# PCB-MicroTally.net
KiCad netlist of a schematic drawn in EAGLE
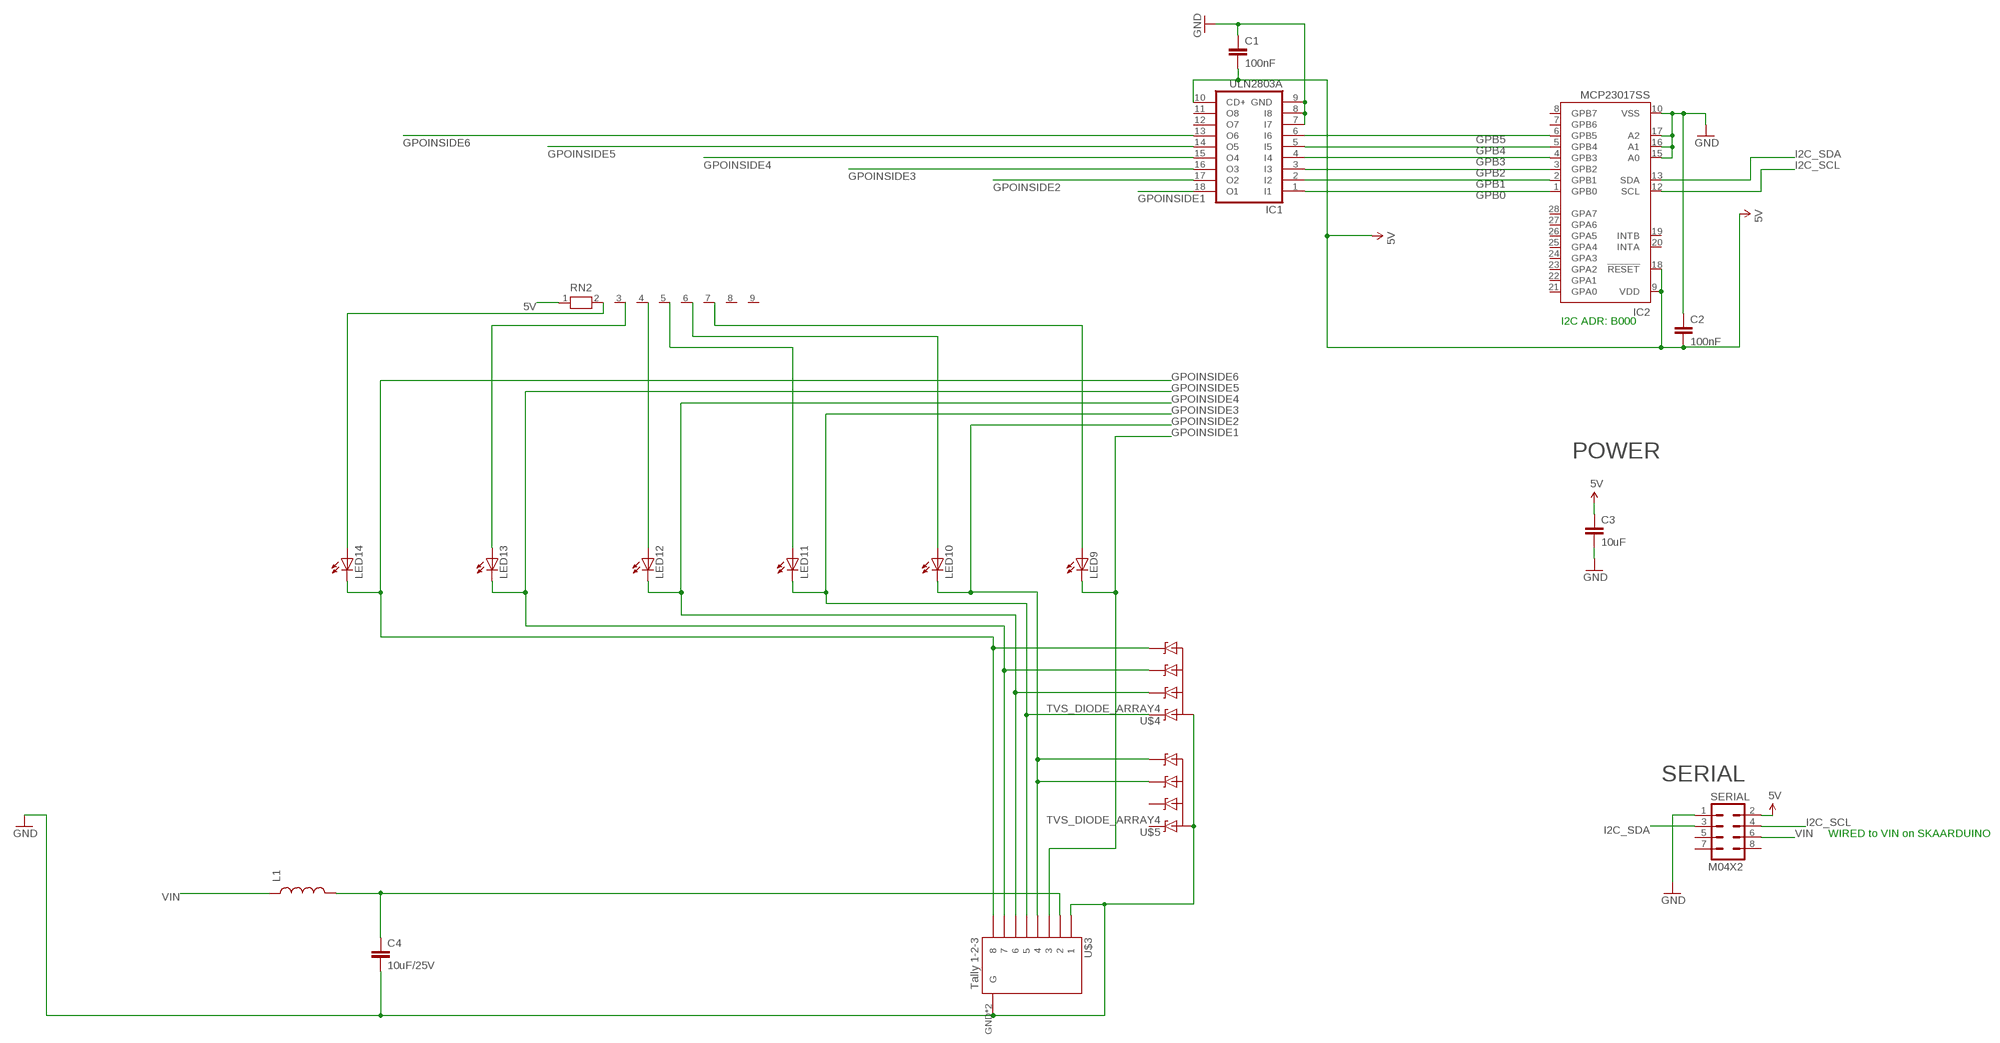
[diagram p0: schematic, sheet 1]

(export (version "E")
  (design (tool "Eeschema 10.0.6"))
  (components
    (comp (ref "C1")
      (value "100nF")
      (footprint "eagle-import:0805")
      (libsource (lib "eagle-import") (part "CAP0805"))
    )
    (comp (ref "C2")
      (value "100nF")
      (footprint "eagle-import:0603-CAP")
      (libsource (lib "eagle-import") (part "CAP0603-CAP"))
    )
    (comp (ref "C3")
      (value "10uF")
      (footprint "eagle-import:0805")
      (libsource (lib "eagle-import") (part "CAP0805"))
    )
    (comp (ref "C4")
      (value "10uF/25V")
      (footprint "eagle-import:0805")
      (libsource (lib "eagle-import") (part "CAP0805"))
    )
    (comp (ref "IC1")
      (value "ULN2803A")
      (footprint "eagle-import:SO18W")
      (libsource (lib "eagle-import") (part "ULN2803ASO18W"))
    )
    (comp (ref "IC2")
      (value "MCP23017SS")
      (footprint "eagle-import:SSOP28")
      (fields (field (name "MF") "MICROCHIP") (field (name "MPN") "MCP23017-E/SS"))
      (libsource (lib "eagle-import") (part "MCP23017SS"))
    )
    (comp (ref "L1")
      (value "INDUCTOR0805")
      (footprint "eagle-import:0805")
      (libsource (lib "eagle-import") (part "INDUCTOR0805"))
    )
    (comp (ref "LED9")
      (value "LED3MM")
      (footprint "eagle-import:LED3MM")
      (libsource (lib "eagle-import") (part "LED3MM"))
    )
    (comp (ref "LED10")
      (value "LED3MM")
      (footprint "eagle-import:LED3MM")
      (libsource (lib "eagle-import") (part "LED3MM"))
    )
    (comp (ref "LED11")
      (value "LED3MM")
      (footprint "eagle-import:LED3MM")
      (libsource (lib "eagle-import") (part "LED3MM"))
    )
    (comp (ref "LED12")
      (value "LED3MM")
      (footprint "eagle-import:LED3MM")
      (libsource (lib "eagle-import") (part "LED3MM"))
    )
    (comp (ref "LED13")
      (value "LED3MM")
      (footprint "eagle-import:LED3MM")
      (libsource (lib "eagle-import") (part "LED3MM"))
    )
    (comp (ref "LED14")
      (value "LED3MM")
      (footprint "eagle-import:LED3MM")
      (libsource (lib "eagle-import") (part "LED3MM"))
    )
    (comp (ref "RN2")
      (value "RN08")
      (footprint "eagle-import:RN-9")
      (libsource (lib "eagle-import") (part "RN08"))
    )
    (comp (ref "SERIAL")
      (value "M04X2")
      (footprint "eagle-import:2X4")
      (libsource (lib "eagle-import") (part "M04X2"))
    )
    (comp (ref "U$3")
      (value "Tally 1-2-3")
      (footprint "eagle-import:RJ45-8_GND_UPRIGHT")
      (libsource (lib "eagle-import") (part "RJ45-8_GNDUPRIGHT"))
    )
    (comp (ref "U$4")
      (value "TVS_DIODE_ARRAY4")
      (footprint "eagle-import:SOT23-6L")
      (libsource (lib "eagle-import") (part "TVS_DIODE_ARRAY4"))
    )
    (comp (ref "U$5")
      (value "TVS_DIODE_ARRAY4")
      (footprint "eagle-import:SOT23-6L")
      (libsource (lib "eagle-import") (part "TVS_DIODE_ARRAY4"))
    )
  )
  (nets
    (net (code "1") (name "/GPB0") (class "Default")
      (node (ref "IC1") (pin "1") (pinfunction "I1_1") (pintype "input"))
      (node (ref "IC2") (pin "1") (pinfunction "GPB0_1") (pintype "bidirectional"))
    )
    (net (code "2") (name "/GPB1") (class "Default")
      (node (ref "IC1") (pin "2") (pinfunction "I2_2") (pintype "input"))
      (node (ref "IC2") (pin "2") (pinfunction "GPB1_2") (pintype "bidirectional"))
    )
    (net (code "3") (name "/GPB2") (class "Default")
      (node (ref "IC1") (pin "3") (pinfunction "I3_3") (pintype "input"))
      (node (ref "IC2") (pin "3") (pinfunction "GPB2_3") (pintype "bidirectional"))
    )
    (net (code "4") (name "/GPB3") (class "Default")
      (node (ref "IC1") (pin "4") (pinfunction "I4_4") (pintype "input"))
      (node (ref "IC2") (pin "4") (pinfunction "GPB3_4") (pintype "bidirectional"))
    )
    (net (code "5") (name "/GPB4") (class "Default")
      (node (ref "IC1") (pin "5") (pinfunction "I5_5") (pintype "input"))
      (node (ref "IC2") (pin "5") (pinfunction "GPB4_5") (pintype "bidirectional"))
    )
    (net (code "6") (name "/GPB5") (class "Default")
      (node (ref "IC1") (pin "6") (pinfunction "I6_6") (pintype "input"))
      (node (ref "IC2") (pin "6") (pinfunction "GPB5_6") (pintype "bidirectional"))
    )
    (net (code "7") (name "/GPOINSIDE1") (class "Default")
      (node (ref "IC1") (pin "18") (pinfunction "O1_18") (pintype "open_collector"))
      (node (ref "LED9") (pin "K") (pinfunction "C_K") (pintype "passive"))
      (node (ref "U$3") (pin "3") (pinfunction "3_3") (pintype "bidirectional"))
    )
    (net (code "8") (name "/GPOINSIDE2") (class "Default")
      (node (ref "IC1") (pin "17") (pinfunction "O2_17") (pintype "open_collector"))
      (node (ref "LED10") (pin "K") (pinfunction "C_K") (pintype "passive"))
      (node (ref "U$3") (pin "4") (pinfunction "4_4") (pintype "bidirectional"))
      (node (ref "U$5") (pin "4") (pinfunction "C_4") (pintype "passive"))
      (node (ref "U$5") (pin "6") (pinfunction "D_6") (pintype "passive"))
    )
    (net (code "9") (name "/GPOINSIDE3") (class "Default")
      (node (ref "IC1") (pin "16") (pinfunction "O3_16") (pintype "open_collector"))
      (node (ref "LED11") (pin "K") (pinfunction "C_K") (pintype "passive"))
      (node (ref "U$3") (pin "5") (pinfunction "5_5") (pintype "bidirectional"))
      (node (ref "U$4") (pin "1") (pinfunction "A_1") (pintype "passive"))
    )
    (net (code "10") (name "/GPOINSIDE4") (class "Default")
      (node (ref "IC1") (pin "15") (pinfunction "O4_15") (pintype "open_collector"))
      (node (ref "LED12") (pin "K") (pinfunction "C_K") (pintype "passive"))
      (node (ref "U$3") (pin "6") (pinfunction "6_6") (pintype "bidirectional"))
      (node (ref "U$4") (pin "3") (pinfunction "B_3") (pintype "passive"))
    )
    (net (code "11") (name "/GPOINSIDE5") (class "Default")
      (node (ref "IC1") (pin "14") (pinfunction "O5_14") (pintype "open_collector"))
      (node (ref "LED13") (pin "K") (pinfunction "C_K") (pintype "passive"))
      (node (ref "U$3") (pin "7") (pinfunction "7_7") (pintype "bidirectional"))
      (node (ref "U$4") (pin "4") (pinfunction "C_4") (pintype "passive"))
    )
    (net (code "12") (name "/GPOINSIDE6") (class "Default")
      (node (ref "IC1") (pin "13") (pinfunction "O6_13") (pintype "open_collector"))
      (node (ref "LED14") (pin "K") (pinfunction "C_K") (pintype "passive"))
      (node (ref "U$3") (pin "8") (pinfunction "8_8") (pintype "bidirectional"))
      (node (ref "U$4") (pin "6") (pinfunction "D_6") (pintype "passive"))
    )
    (net (code "13") (name "/I2C_SCL") (class "Default")
      (node (ref "IC2") (pin "12") (pinfunction "SCL_12") (pintype "input"))
      (node (ref "SERIAL") (pin "4") (pinfunction "4_4") (pintype "passive"))
    )
    (net (code "14") (name "/I2C_SDA") (class "Default")
      (node (ref "IC2") (pin "13") (pinfunction "SDA_13") (pintype "bidirectional"))
      (node (ref "SERIAL") (pin "3") (pinfunction "3_3") (pintype "passive"))
    )
    (net (code "15") (name "/VIN") (class "Default")
      (node (ref "L1") (pin "1") (pinfunction "1_1") (pintype "passive"))
      (node (ref "SERIAL") (pin "6") (pinfunction "6_6") (pintype "passive"))
    )
    (net (code "16") (name "5V") (class "Default")
      (node (ref "C1") (pin "2") (pinfunction "2_2") (pintype "passive"))
      (node (ref "C2") (pin "2") (pinfunction "2_2") (pintype "passive"))
      (node (ref "C3") (pin "1") (pinfunction "1_1") (pintype "passive"))
      (node (ref "IC1") (pin "10") (pinfunction "CD+_10") (pintype "passive"))
      (node (ref "IC2") (pin "18") (pinfunction "~{RESET}_18") (pintype "input"))
      (node (ref "IC2") (pin "9") (pinfunction "VDD_9") (pintype "power_in"))
      (node (ref "RN2") (pin "1") (pinfunction "1_1") (pintype "passive"))
      (node (ref "SERIAL") (pin "2") (pinfunction "2_2") (pintype "passive"))
    )
    (net (code "17") (name "GND") (class "Default")
      (node (ref "C1") (pin "1") (pinfunction "1_1") (pintype "passive"))
      (node (ref "C2") (pin "1") (pinfunction "1_1") (pintype "passive"))
      (node (ref "C3") (pin "2") (pinfunction "2_2") (pintype "passive"))
      (node (ref "C4") (pin "2") (pinfunction "2_2") (pintype "passive"))
      (node (ref "IC1") (pin "7") (pinfunction "I7_7") (pintype "input"))
      (node (ref "IC1") (pin "8") (pinfunction "I8_8") (pintype "input"))
      (node (ref "IC1") (pin "9") (pinfunction "GND_9") (pintype "power_in"))
      (node (ref "IC2") (pin "10") (pinfunction "VSS_10") (pintype "power_in"))
      (node (ref "IC2") (pin "15") (pinfunction "A0_15") (pintype "input"))
      (node (ref "IC2") (pin "16") (pinfunction "A1_16") (pintype "input"))
      (node (ref "IC2") (pin "17") (pinfunction "A2_17") (pintype "input"))
      (node (ref "SERIAL") (pin "1") (pinfunction "1_1") (pintype "passive"))
      (node (ref "U$3") (pin "1") (pinfunction "1_1") (pintype "bidirectional"))
      (node (ref "U$3") (pin "GND") (pinfunction "G_GND") (pintype "power_in"))
      (node (ref "U$3") (pin "GND1") (pinfunction "G_GND1") (pintype "power_in"))
      (node (ref "U$4") (pin "2") (pinfunction "GND_2") (pintype "passive"))
      (node (ref "U$4") (pin "5") (pinfunction "GND_5") (pintype "passive"))
      (node (ref "U$5") (pin "2") (pinfunction "GND_2") (pintype "passive"))
      (node (ref "U$5") (pin "5") (pinfunction "GND_5") (pintype "passive"))
    )
    (net (code "18") (name "Net-(C4-Pad1)") (class "Default")
      (node (ref "C4") (pin "1") (pinfunction "1_1") (pintype "passive"))
      (node (ref "L1") (pin "2") (pinfunction "2_2") (pintype "passive"))
      (node (ref "U$3") (pin "2") (pinfunction "2_2") (pintype "bidirectional"))
    )
    (net (code "19") (name "Net-(LED9-PadA)") (class "Default")
      (node (ref "LED9") (pin "A") (pinfunction "A_A") (pintype "passive"))
      (node (ref "RN2") (pin "7") (pinfunction "7_7") (pintype "passive"))
    )
    (net (code "20") (name "Net-(LED10-PadA)") (class "Default")
      (node (ref "LED10") (pin "A") (pinfunction "A_A") (pintype "passive"))
      (node (ref "RN2") (pin "6") (pinfunction "6_6") (pintype "passive"))
    )
    (net (code "21") (name "Net-(LED11-PadA)") (class "Default")
      (node (ref "LED11") (pin "A") (pinfunction "A_A") (pintype "passive"))
      (node (ref "RN2") (pin "5") (pinfunction "5_5") (pintype "passive"))
    )
    (net (code "22") (name "Net-(LED12-PadA)") (class "Default")
      (node (ref "LED12") (pin "A") (pinfunction "A_A") (pintype "passive"))
      (node (ref "RN2") (pin "4") (pinfunction "4_4") (pintype "passive"))
    )
    (net (code "23") (name "Net-(LED13-PadA)") (class "Default")
      (node (ref "LED13") (pin "A") (pinfunction "A_A") (pintype "passive"))
      (node (ref "RN2") (pin "3") (pinfunction "3_3") (pintype "passive"))
    )
    (net (code "24") (name "Net-(LED14-PadA)") (class "Default")
      (node (ref "LED14") (pin "A") (pinfunction "A_A") (pintype "passive"))
      (node (ref "RN2") (pin "2") (pinfunction "2_2") (pintype "passive"))
    )
    (net (code "25") (name "unconnected-(IC1-O7-Pad12)") (class "Default")
      (node (ref "IC1") (pin "12") (pinfunction "O7_12") (pintype "open_collector"))
    )
    (net (code "26") (name "unconnected-(IC1-O8-Pad11)") (class "Default")
      (node (ref "IC1") (pin "11") (pinfunction "O8_11") (pintype "open_collector"))
    )
    (net (code "27") (name "unconnected-(IC2-GPA0-Pad21)") (class "Default")
      (node (ref "IC2") (pin "21") (pinfunction "GPA0_21") (pintype "bidirectional"))
    )
    (net (code "28") (name "unconnected-(IC2-GPA1-Pad22)") (class "Default")
      (node (ref "IC2") (pin "22") (pinfunction "GPA1_22") (pintype "bidirectional"))
    )
    (net (code "29") (name "unconnected-(IC2-GPA2-Pad23)") (class "Default")
      (node (ref "IC2") (pin "23") (pinfunction "GPA2_23") (pintype "bidirectional"))
    )
    (net (code "30") (name "unconnected-(IC2-GPA3-Pad24)") (class "Default")
      (node (ref "IC2") (pin "24") (pinfunction "GPA3_24") (pintype "bidirectional"))
    )
    (net (code "31") (name "unconnected-(IC2-GPA4-Pad25)") (class "Default")
      (node (ref "IC2") (pin "25") (pinfunction "GPA4_25") (pintype "bidirectional"))
    )
    (net (code "32") (name "unconnected-(IC2-GPA5-Pad26)") (class "Default")
      (node (ref "IC2") (pin "26") (pinfunction "GPA5_26") (pintype "bidirectional"))
    )
    (net (code "33") (name "unconnected-(IC2-GPA6-Pad27)") (class "Default")
      (node (ref "IC2") (pin "27") (pinfunction "GPA6_27") (pintype "bidirectional"))
    )
    (net (code "34") (name "unconnected-(IC2-GPA7-Pad28)") (class "Default")
      (node (ref "IC2") (pin "28") (pinfunction "GPA7_28") (pintype "bidirectional"))
    )
    (net (code "35") (name "unconnected-(IC2-GPB6-Pad7)") (class "Default")
      (node (ref "IC2") (pin "7") (pinfunction "GPB6_7") (pintype "bidirectional"))
    )
    (net (code "36") (name "unconnected-(IC2-GPB7-Pad8)") (class "Default")
      (node (ref "IC2") (pin "8") (pinfunction "GPB7_8") (pintype "bidirectional"))
    )
    (net (code "37") (name "unconnected-(IC2-INTA-Pad20)") (class "Default")
      (node (ref "IC2") (pin "20") (pinfunction "INTA_20") (pintype "output"))
    )
    (net (code "38") (name "unconnected-(IC2-INTB-Pad19)") (class "Default")
      (node (ref "IC2") (pin "19") (pinfunction "INTB_19") (pintype "output"))
    )
    (net (code "39") (name "unconnected-(RN2-Pad8)") (class "Default")
      (node (ref "RN2") (pin "8") (pinfunction "8_8") (pintype "passive"))
    )
    (net (code "40") (name "unconnected-(RN2-Pad9)") (class "Default")
      (node (ref "RN2") (pin "9") (pinfunction "9_9") (pintype "passive"))
    )
    (net (code "41") (name "unconnected-(SERIAL-Pad5)") (class "Default")
      (node (ref "SERIAL") (pin "5") (pinfunction "5_5") (pintype "passive"))
    )
    (net (code "42") (name "unconnected-(SERIAL-Pad7)") (class "Default")
      (node (ref "SERIAL") (pin "7") (pinfunction "7_7") (pintype "passive"))
    )
    (net (code "43") (name "unconnected-(SERIAL-Pad8)") (class "Default")
      (node (ref "SERIAL") (pin "8") (pinfunction "8_8") (pintype "passive"))
    )
    (net (code "44") (name "unconnected-(U$5-A-Pad1)") (class "Default")
      (node (ref "U$5") (pin "1") (pinfunction "A_1") (pintype "passive"))
    )
    (net (code "45") (name "unconnected-(U$5-B-Pad3)") (class "Default")
      (node (ref "U$5") (pin "3") (pinfunction "B_3") (pintype "passive"))
    )
  )
)
